# SCH_GPS_2026-03-24.net
KiCad netlist of a schematic drawn in EasyEDA
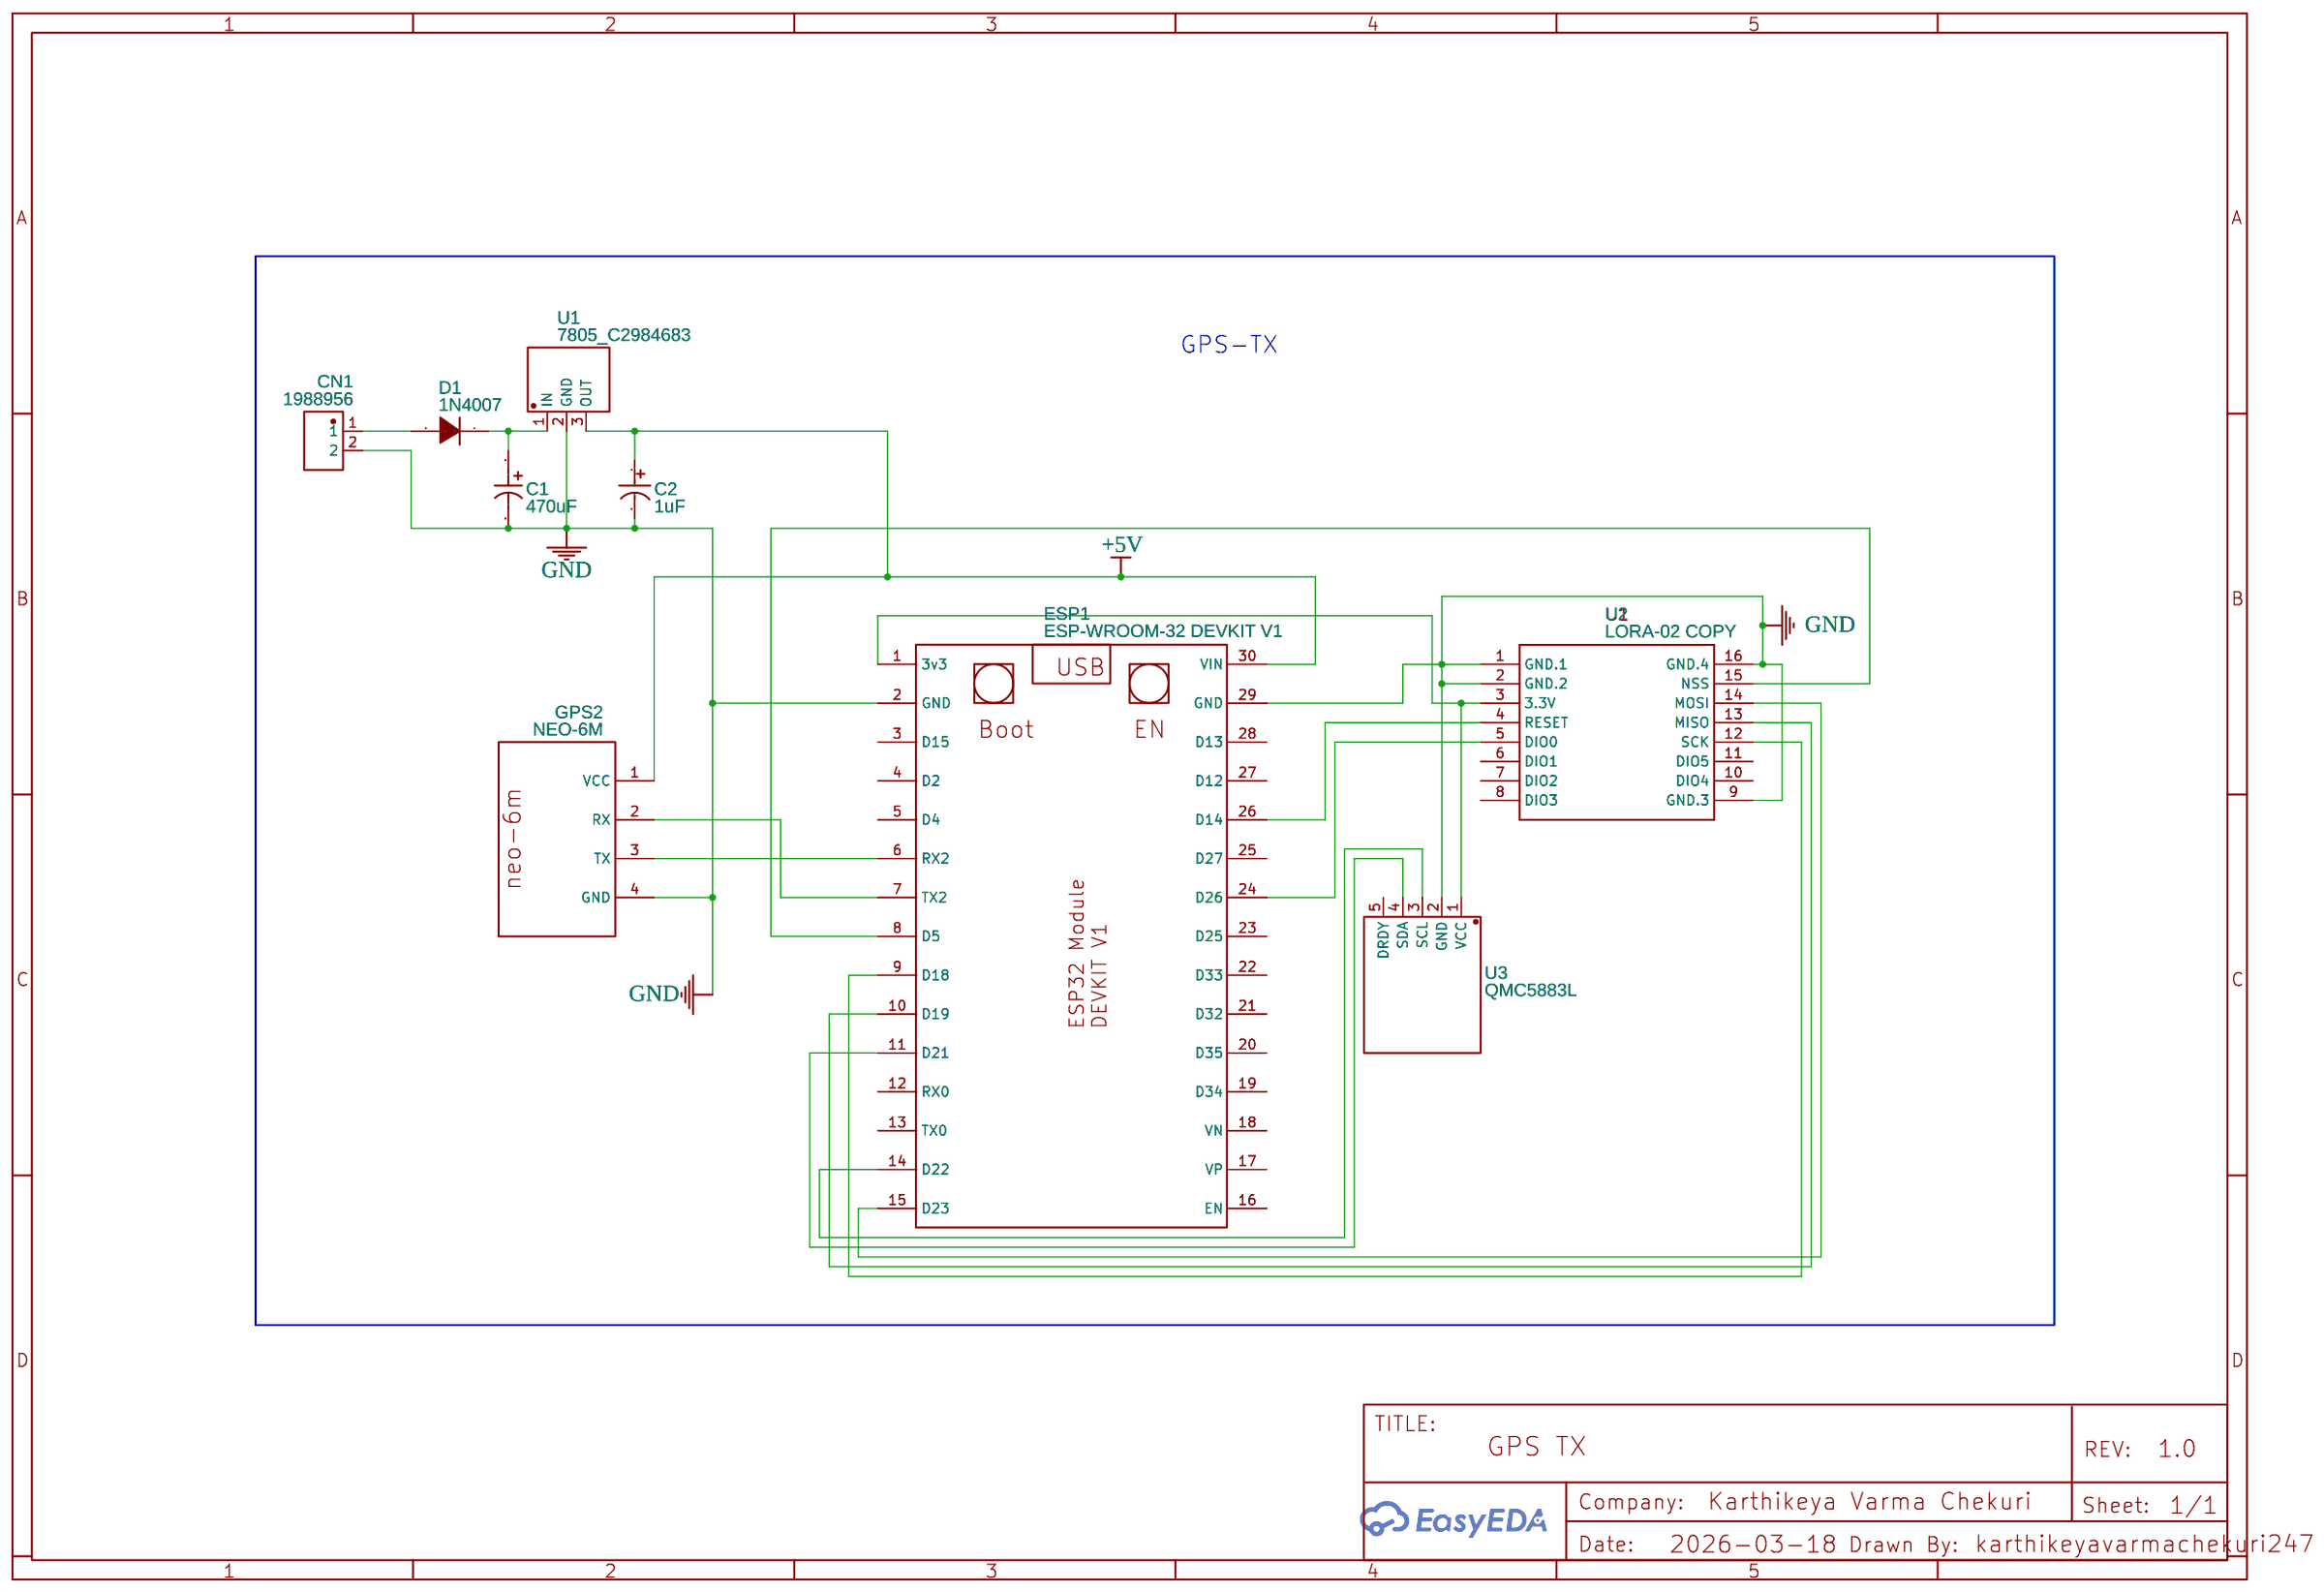
[diagram p0: schematic sheet]

(export (version "E")
  (design (tool "Eeschema 10.0.6"))
  (components
    (comp (ref "C1")
      (value "470uF")
      (fields (field (name "Manufacturer Part") "470UF25VF140KM") (field (name "Manufacturer") "Econd(米朗电子)"))
      (libsource (lib "") (part "470UF25VF140KM"))
    )
    (comp (ref "C2")
      (value "1uF")
      (fields
        (field (name "Manufacturer Part") "KM105M400E12RR0VH2FP0")
        (field (name "Manufacturer") "Chengx(承兴)")
      )
      (libsource (lib "") (part "1uF 400V 6.3*12"))
    )
    (comp (ref "CN1")
      (value "1988956")
      (fields (field (name "Manufacturer") "Phoenix Contact(菲尼克斯)"))
      (libsource (lib "") (part "1988956"))
    )
    (comp (ref "D1")
      (value "1N4007")
      (fields (field (name "Manufacturer") "ST(先科)"))
      (libsource (lib "") (part "1N4007"))
    )
    (comp (ref "ESP1") (value "ESP-WROOM-32 DEVKIT V1") (libsource (lib "") (part "ESP-WROOM-32 DEVKIT V1")))
    (comp (ref "GPS2") (value "NEO-6M") (libsource (lib "") (part "NEO-6M")))
    (comp (ref "U1")
      (value "7805_C2984683")
      (fields (field (name "Manufacturer Part") "7805") (field (name "Manufacturer") "集晶电子"))
      (libsource (lib "") (part "7805_C2984683"))
    )
    (comp (ref "U2") (value "LORA-02 COPY") (libsource (lib "") (part "LORA-02 COPY")))
    (comp (ref "U3") (value "QMC5883L") (libsource (lib "") (part "QMC5883L")))
  )
  (nets
    (net (code "1") (name "+5V") (class "Default")
      (node (ref "C2") (pin "1") (pinfunction "1_1") (pintype "input"))
      (node (ref "ESP1") (pin "30") (pinfunction "VIN_30") (pintype "unspecified"))
      (node (ref "GPS2") (pin "1") (pinfunction "VCC_1") (pintype "unspecified"))
      (node (ref "U1") (pin "3") (pinfunction "OUT_3") (pintype "unspecified"))
    )
    (net (code "2") (name "GND") (class "Default")
      (node (ref "C1") (pin "2") (pinfunction "2_2") (pintype "input"))
      (node (ref "C2") (pin "2") (pinfunction "2_2") (pintype "input"))
      (node (ref "CN1") (pin "2") (pinfunction "2_2") (pintype "unspecified"))
      (node (ref "ESP1") (pin "2") (pinfunction "GND_2") (pintype "unspecified"))
      (node (ref "ESP1") (pin "29") (pinfunction "GND_29") (pintype "unspecified"))
      (node (ref "GPS2") (pin "4") (pinfunction "GND_4") (pintype "unspecified"))
      (node (ref "U1") (pin "2") (pinfunction "GND_2") (pintype "unspecified"))
      (node (ref "U2") (pin "1") (pinfunction "GND.1_1") (pintype "passive"))
      (node (ref "U2") (pin "16") (pinfunction "GND.4_16") (pintype "passive"))
      (node (ref "U2") (pin "2") (pinfunction "GND.2_2") (pintype "passive"))
      (node (ref "U2") (pin "9") (pinfunction "GND.3_9") (pintype "passive"))
      (node (ref "U3") (pin "2") (pinfunction "GND_2") (pintype "unspecified"))
    )
    (net (code "3") (name "Net-(D1-A)") (class "Default")
      (node (ref "CN1") (pin "1") (pinfunction "1_1") (pintype "unspecified"))
      (node (ref "D1") (pin "2") (pinfunction "A_2") (pintype "unspecified"))
    )
    (net (code "4") (name "Net-(D1-K)") (class "Default")
      (node (ref "C1") (pin "1") (pinfunction "1_1") (pintype "input"))
      (node (ref "D1") (pin "1") (pinfunction "K_1") (pintype "unspecified"))
      (node (ref "U1") (pin "1") (pinfunction "IN_1") (pintype "unspecified"))
    )
    (net (code "5") (name "Net-(ESP1-3v3)") (class "Default")
      (node (ref "ESP1") (pin "1") (pinfunction "3v3_1") (pintype "unspecified"))
      (node (ref "U2") (pin "3") (pinfunction "3.3V_3") (pintype "passive"))
      (node (ref "U3") (pin "1") (pinfunction "VCC_1") (pintype "unspecified"))
    )
    (net (code "6") (name "Net-(ESP1-D5)") (class "Default")
      (node (ref "ESP1") (pin "8") (pinfunction "D5_8") (pintype "unspecified"))
      (node (ref "U2") (pin "15") (pinfunction "NSS_15") (pintype "unspecified"))
    )
    (net (code "7") (name "Net-(ESP1-D14)") (class "Default")
      (node (ref "ESP1") (pin "26") (pinfunction "D14_26") (pintype "unspecified"))
      (node (ref "U2") (pin "4") (pinfunction "RESET_4") (pintype "unspecified"))
    )
    (net (code "8") (name "Net-(ESP1-D18)") (class "Default")
      (node (ref "ESP1") (pin "9") (pinfunction "D18_9") (pintype "unspecified"))
      (node (ref "U2") (pin "12") (pinfunction "SCK_12") (pintype "unspecified"))
    )
    (net (code "9") (name "Net-(ESP1-D19)") (class "Default")
      (node (ref "ESP1") (pin "10") (pinfunction "D19_10") (pintype "unspecified"))
      (node (ref "U2") (pin "13") (pinfunction "MISO_13") (pintype "unspecified"))
    )
    (net (code "10") (name "Net-(ESP1-D21)") (class "Default")
      (node (ref "ESP1") (pin "11") (pinfunction "D21_11") (pintype "unspecified"))
      (node (ref "U3") (pin "4") (pinfunction "SDA_4") (pintype "unspecified"))
    )
    (net (code "11") (name "Net-(ESP1-D22)") (class "Default")
      (node (ref "ESP1") (pin "14") (pinfunction "D22_14") (pintype "unspecified"))
      (node (ref "U3") (pin "3") (pinfunction "SCL_3") (pintype "unspecified"))
    )
    (net (code "12") (name "Net-(ESP1-D23)") (class "Default")
      (node (ref "ESP1") (pin "15") (pinfunction "D23_15") (pintype "unspecified"))
      (node (ref "U2") (pin "14") (pinfunction "MOSI_14") (pintype "unspecified"))
    )
    (net (code "13") (name "Net-(ESP1-D26)") (class "Default")
      (node (ref "ESP1") (pin "24") (pinfunction "D26_24") (pintype "unspecified"))
      (node (ref "U2") (pin "5") (pinfunction "DIO0_5") (pintype "unspecified"))
    )
    (net (code "14") (name "Net-(ESP1-RX2)") (class "Default")
      (node (ref "ESP1") (pin "6") (pinfunction "RX2_6") (pintype "unspecified"))
      (node (ref "GPS2") (pin "3") (pinfunction "TX_3") (pintype "unspecified"))
    )
    (net (code "15") (name "Net-(ESP1-TX2)") (class "Default")
      (node (ref "ESP1") (pin "7") (pinfunction "TX2_7") (pintype "unspecified"))
      (node (ref "GPS2") (pin "2") (pinfunction "RX_2") (pintype "unspecified"))
    )
    (net (code "16") (name "unconnected-(ESP1-D2-Pad4)") (class "Default")
      (node (ref "ESP1") (pin "4") (pinfunction "D2_4") (pintype "unspecified"))
    )
    (net (code "17") (name "unconnected-(ESP1-D4-Pad5)") (class "Default")
      (node (ref "ESP1") (pin "5") (pinfunction "D4_5") (pintype "unspecified"))
    )
    (net (code "18") (name "unconnected-(ESP1-D12-Pad27)") (class "Default")
      (node (ref "ESP1") (pin "27") (pinfunction "D12_27") (pintype "unspecified"))
    )
    (net (code "19") (name "unconnected-(ESP1-D13-Pad28)") (class "Default")
      (node (ref "ESP1") (pin "28") (pinfunction "D13_28") (pintype "unspecified"))
    )
    (net (code "20") (name "unconnected-(ESP1-D15-Pad3)") (class "Default")
      (node (ref "ESP1") (pin "3") (pinfunction "D15_3") (pintype "unspecified"))
    )
    (net (code "21") (name "unconnected-(ESP1-D25-Pad23)") (class "Default")
      (node (ref "ESP1") (pin "23") (pinfunction "D25_23") (pintype "unspecified"))
    )
    (net (code "22") (name "unconnected-(ESP1-D27-Pad25)") (class "Default")
      (node (ref "ESP1") (pin "25") (pinfunction "D27_25") (pintype "unspecified"))
    )
    (net (code "23") (name "unconnected-(ESP1-D32-Pad21)") (class "Default")
      (node (ref "ESP1") (pin "21") (pinfunction "D32_21") (pintype "unspecified"))
    )
    (net (code "24") (name "unconnected-(ESP1-D33-Pad22)") (class "Default")
      (node (ref "ESP1") (pin "22") (pinfunction "D33_22") (pintype "unspecified"))
    )
    (net (code "25") (name "unconnected-(ESP1-D34-Pad19)") (class "Default")
      (node (ref "ESP1") (pin "19") (pinfunction "D34_19") (pintype "unspecified"))
    )
    (net (code "26") (name "unconnected-(ESP1-D35-Pad20)") (class "Default")
      (node (ref "ESP1") (pin "20") (pinfunction "D35_20") (pintype "unspecified"))
    )
    (net (code "27") (name "unconnected-(ESP1-EN-Pad16)") (class "Default")
      (node (ref "ESP1") (pin "16") (pinfunction "EN_16") (pintype "unspecified"))
    )
    (net (code "28") (name "unconnected-(ESP1-RX0-Pad12)") (class "Default")
      (node (ref "ESP1") (pin "12") (pinfunction "RX0_12") (pintype "unspecified"))
    )
    (net (code "29") (name "unconnected-(ESP1-TX0-Pad13)") (class "Default")
      (node (ref "ESP1") (pin "13") (pinfunction "TX0_13") (pintype "unspecified"))
    )
    (net (code "30") (name "unconnected-(ESP1-VN-Pad18)") (class "Default")
      (node (ref "ESP1") (pin "18") (pinfunction "VN_18") (pintype "unspecified"))
    )
    (net (code "31") (name "unconnected-(ESP1-VP-Pad17)") (class "Default")
      (node (ref "ESP1") (pin "17") (pinfunction "VP_17") (pintype "unspecified"))
    )
    (net (code "32") (name "unconnected-(U2-DIO1-Pad6)") (class "Default")
      (node (ref "U2") (pin "6") (pinfunction "DIO1_6") (pintype "unspecified"))
    )
    (net (code "33") (name "unconnected-(U2-DIO2-Pad7)") (class "Default")
      (node (ref "U2") (pin "7") (pinfunction "DIO2_7") (pintype "unspecified"))
    )
    (net (code "34") (name "unconnected-(U2-DIO3-Pad8)") (class "Default")
      (node (ref "U2") (pin "8") (pinfunction "DIO3_8") (pintype "unspecified"))
    )
    (net (code "35") (name "unconnected-(U2-DIO4-Pad10)") (class "Default")
      (node (ref "U2") (pin "10") (pinfunction "DIO4_10") (pintype "unspecified"))
    )
    (net (code "36") (name "unconnected-(U2-DIO5-Pad11)") (class "Default")
      (node (ref "U2") (pin "11") (pinfunction "DIO5_11") (pintype "unspecified"))
    )
    (net (code "37") (name "unconnected-(U3-DRDY-Pad5)") (class "Default")
      (node (ref "U3") (pin "5") (pinfunction "DRDY_5") (pintype "unspecified"))
    )
  )
)
